# Main_Camera_Board7_with_holes.net
KiCad netlist of a schematic drawn in EAGLE
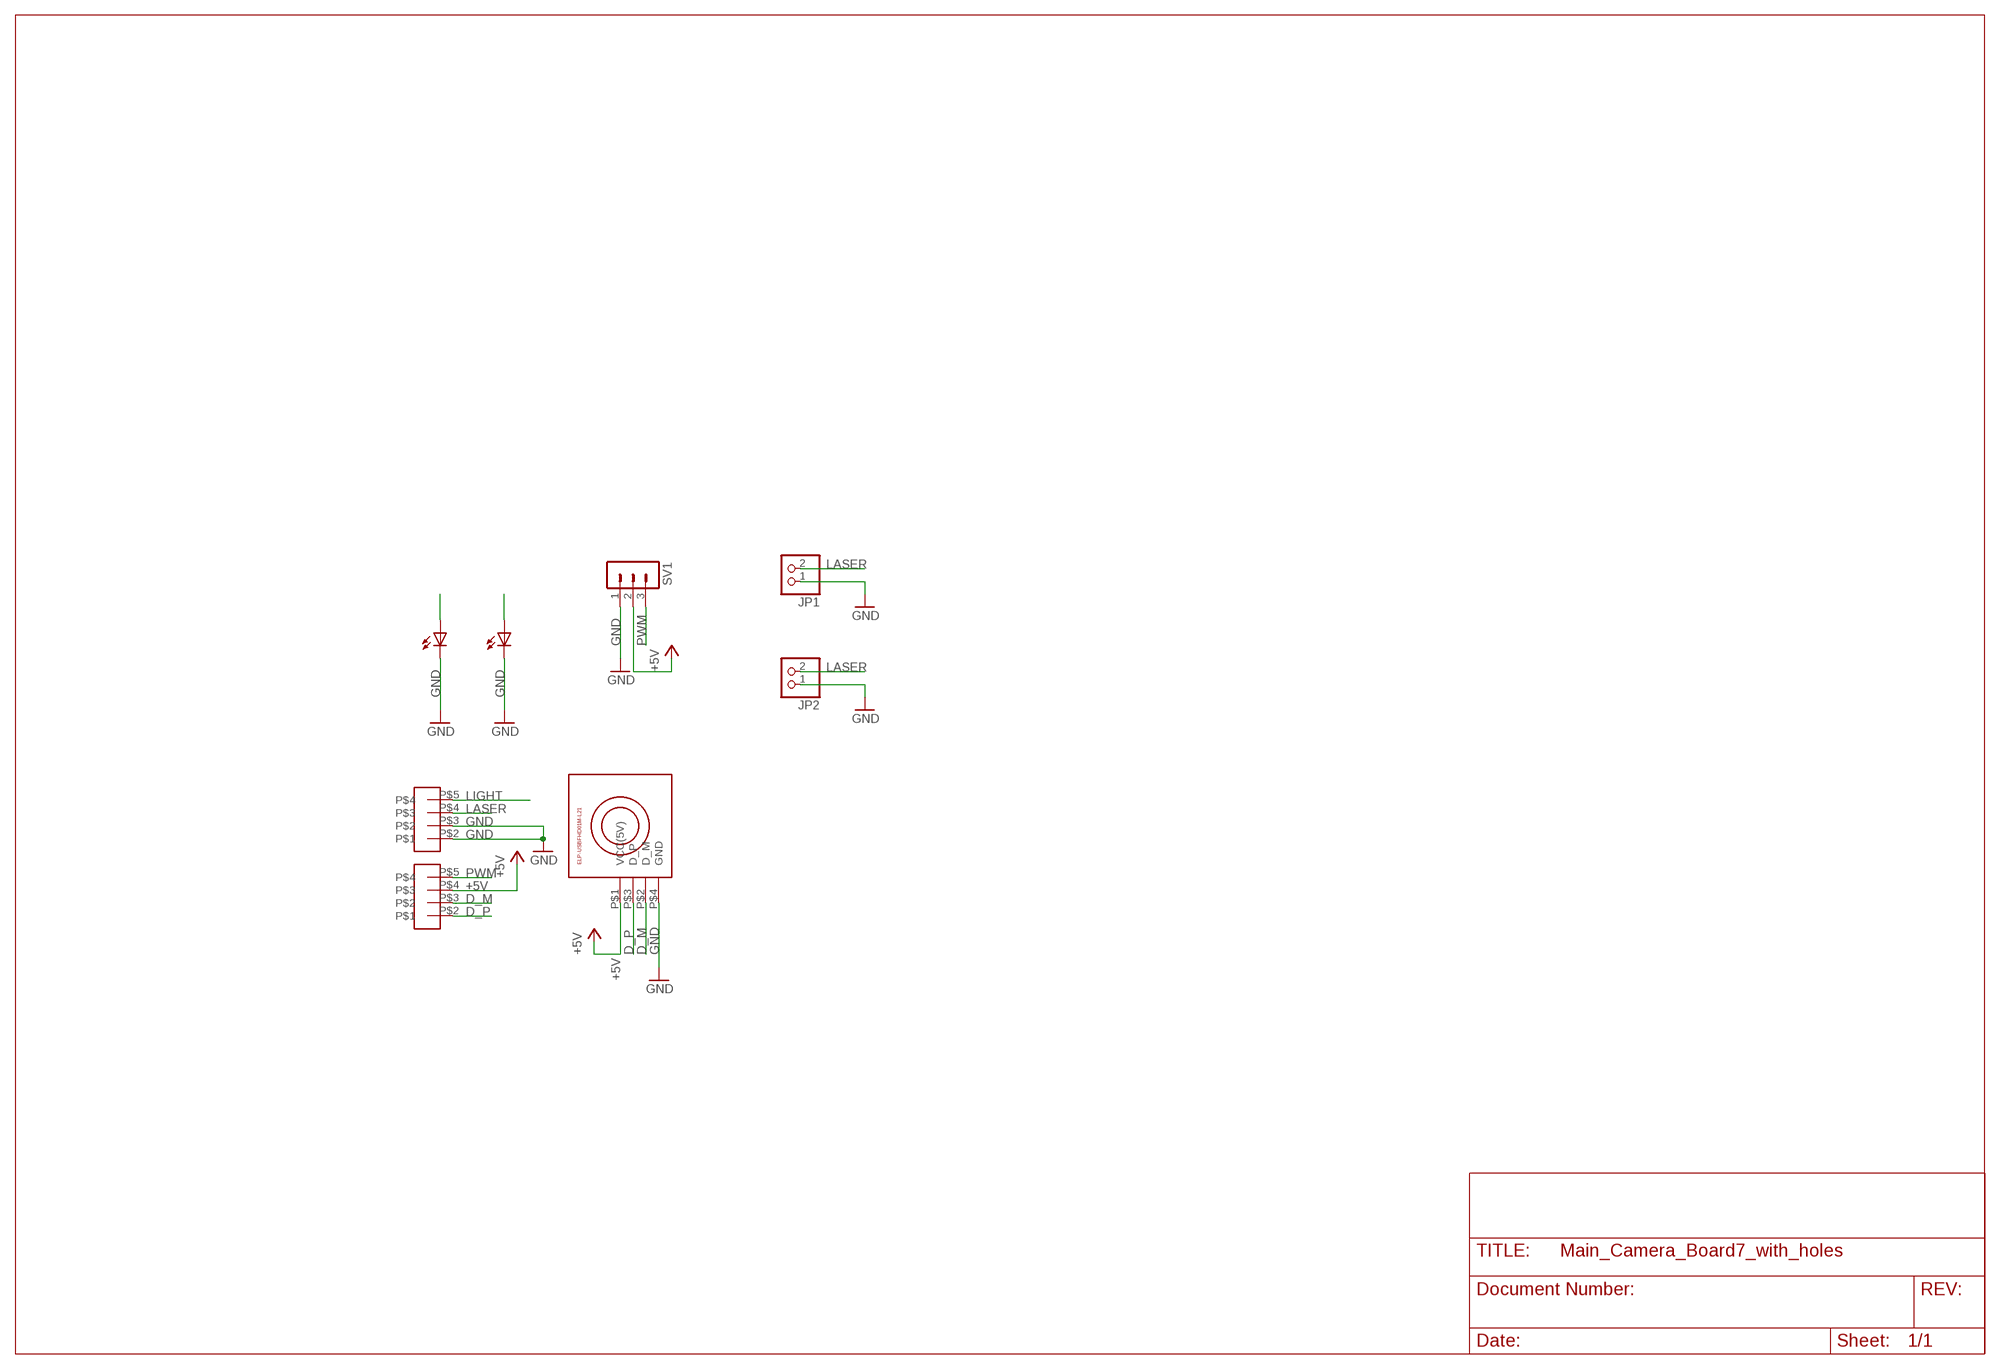
[diagram p0: schematic, sheet 1]

(export (version "E")
  (design (tool "Eeschema 10.0.6"))
  (components
    (comp (ref "JP1")
      (value "PINHD-1X2")
      (footprint "eagle-import:1X02")
      (libsource (lib "eagle-import") (part "PINHD-1X2"))
    )
    (comp (ref "JP2")
      (value "PINHD-1X2")
      (footprint "eagle-import:1X02")
      (libsource (lib "eagle-import") (part "PINHD-1X2"))
    )
    (comp (ref "SV1")
      (value "MA03-1")
      (footprint "eagle-import:MA03-1")
      (libsource (lib "eagle-import") (part "MA03-1"))
    )
    (comp (ref "U$1")
      (value "ELP-USBFHD01M-L21")
      (footprint "eagle-import:ELP-USBFHD01M-L21")
      (libsource (lib "eagle-import") (part "ELP-USBFHD01M-L21"))
    )
    (comp (ref "U$2")
      (value "LED")
      (footprint "eagle-import:LED")
      (libsource (lib "eagle-import") (part "LED"))
    )
    (comp (ref "U$3")
      (value "LED")
      (footprint "eagle-import:LED")
      (libsource (lib "eagle-import") (part "LED"))
    )
    (comp (ref "U$4")
      (value "T21")
      (footprint "eagle-import:T2I")
      (libsource (lib "eagle-import") (part "T21"))
    )
    (comp (ref "U$5")
      (value "T21")
      (footprint "eagle-import:T2I")
      (libsource (lib "eagle-import") (part "T21"))
    )
  )
  (nets
    (net (code "1") (name "+5V") (class "Default")
      (node (ref "SV1") (pin "2") (pinfunction "2_2") (pintype "passive"))
      (node (ref "U$1") (pin "P$1") (pinfunction "VCC(5V)_P$1") (pintype "bidirectional"))
      (node (ref "U$5") (pin "P$4") (pinfunction "P$3_P$4") (pintype "bidirectional"))
    )
    (net (code "2") (name "/D_M") (class "Default")
      (node (ref "U$1") (pin "P$2") (pinfunction "D_M_P$2") (pintype "bidirectional"))
      (node (ref "U$5") (pin "P$3") (pinfunction "P$2_P$3") (pintype "bidirectional"))
    )
    (net (code "3") (name "/D_P") (class "Default")
      (node (ref "U$1") (pin "P$3") (pinfunction "D_P_P$3") (pintype "bidirectional"))
      (node (ref "U$5") (pin "P$2") (pinfunction "P$1_P$2") (pintype "bidirectional"))
    )
    (net (code "4") (name "/LASER") (class "Default")
      (node (ref "JP1") (pin "2") (pinfunction "2_2") (pintype "passive"))
      (node (ref "JP2") (pin "2") (pinfunction "2_2") (pintype "passive"))
      (node (ref "U$4") (pin "P$4") (pinfunction "P$3_P$4") (pintype "bidirectional"))
    )
    (net (code "5") (name "/LIGHT") (class "Default")
      (node (ref "U$2") (pin "P$2") (pinfunction "ANODE_P$2") (pintype "passive"))
      (node (ref "U$3") (pin "P$2") (pinfunction "ANODE_P$2") (pintype "passive"))
      (node (ref "U$4") (pin "P$5") (pinfunction "P$4_P$5") (pintype "bidirectional"))
    )
    (net (code "6") (name "/PWM") (class "Default")
      (node (ref "SV1") (pin "3") (pinfunction "3_3") (pintype "passive"))
      (node (ref "U$5") (pin "P$5") (pinfunction "P$4_P$5") (pintype "bidirectional"))
    )
    (net (code "7") (name "GND") (class "Default")
      (node (ref "JP1") (pin "1") (pinfunction "1_1") (pintype "passive"))
      (node (ref "JP2") (pin "1") (pinfunction "1_1") (pintype "passive"))
      (node (ref "SV1") (pin "1") (pinfunction "1_1") (pintype "passive"))
      (node (ref "U$1") (pin "P$4") (pinfunction "GND_P$4") (pintype "bidirectional"))
      (node (ref "U$2") (pin "P$1") (pinfunction "CATHODE_P$1") (pintype "passive"))
      (node (ref "U$2") (pin "P$3") (pinfunction "CATHODE_P$3") (pintype "passive"))
      (node (ref "U$3") (pin "P$1") (pinfunction "CATHODE_P$1") (pintype "passive"))
      (node (ref "U$3") (pin "P$3") (pinfunction "CATHODE_P$3") (pintype "passive"))
      (node (ref "U$4") (pin "P$2") (pinfunction "P$1_P$2") (pintype "bidirectional"))
      (node (ref "U$4") (pin "P$3") (pinfunction "P$2_P$3") (pintype "bidirectional"))
    )
  )
)
